# BMI160_SCHEMATIC.net
KiCad netlist of a schematic drawn in EAGLE
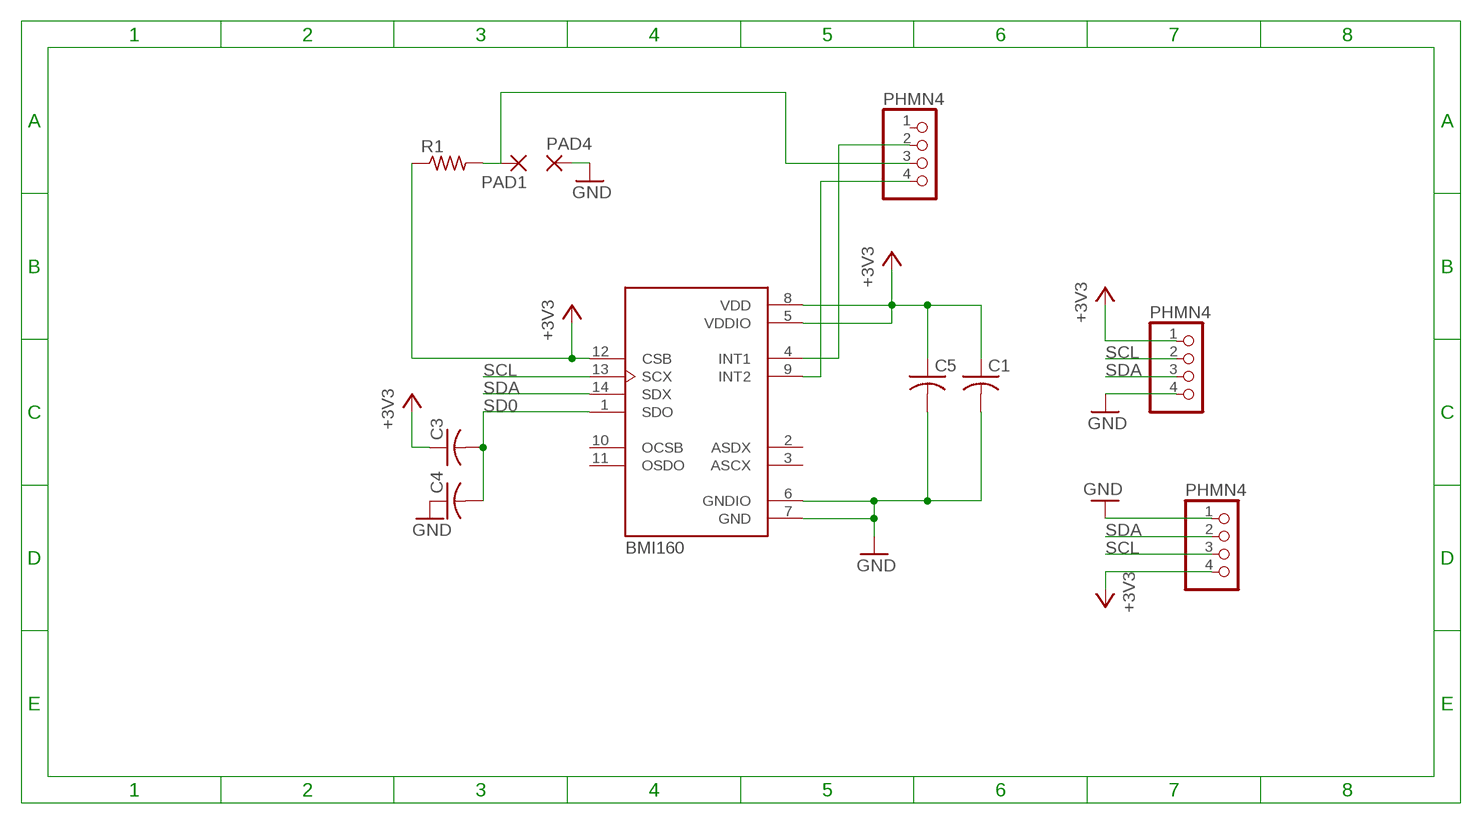
[diagram p0: schematic, sheet 1]

(export (version "E")
  (design (tool "Eeschema 10.0.6"))
  (components
    (comp (ref "C1")
      (value "C-USC0805")
      (footprint "eagle-import:C0805")
      (libsource (lib "eagle-import") (part "C-USC0805"))
    )
    (comp (ref "C3")
      (value "C-USC0805")
      (footprint "eagle-import:C0805")
      (libsource (lib "eagle-import") (part "C-USC0805"))
    )
    (comp (ref "C4")
      (value "C-USC0805")
      (footprint "eagle-import:C0805")
      (libsource (lib "eagle-import") (part "C-USC0805"))
    )
    (comp (ref "C5")
      (value "C-USC0805")
      (footprint "eagle-import:C0805")
      (libsource (lib "eagle-import") (part "C-USC0805"))
    )
    (comp (ref "PAD1")
      (value "WIREPADSMD1,27-254")
      (footprint "eagle-import:SMD1,27-2,54")
      (libsource (lib "eagle-import") (part "WIREPADSMD1,27-254"))
    )
    (comp (ref "PAD4")
      (value "WIREPADSMD1,27-254")
      (footprint "eagle-import:SMD1,27-2,54")
      (libsource (lib "eagle-import") (part "WIREPADSMD1,27-254"))
    )
    (comp (ref "R1")
      (value "CRCW08050000Z0EA")
      (footprint "eagle-import:RES_0805")
      (fields
        (field (name "DIGIKEY_PART_NUMBER") "541-0.0ATR-ND")
        (field (name "MANUFACTURER") "Vishay Dale")
        (field (name "CREATED_BY") "PCBLayout.com")
      )
      (libsource (lib "eagle-import") (part "CRCW08050000Z0EA"))
    )
    (comp (ref "U$1")
      (value "PHMN4")
      (footprint "eagle-import:1X04")
      (libsource (lib "eagle-import") (part "PHMN4"))
    )
    (comp (ref "U$2")
      (value "PHMN4")
      (footprint "eagle-import:1X04")
      (libsource (lib "eagle-import") (part "PHMN4"))
    )
    (comp (ref "U$4")
      (value "PHMN4")
      (footprint "eagle-import:1X04")
      (libsource (lib "eagle-import") (part "PHMN4"))
    )
    (comp (ref "U1")
      (value "BMI160")
      (footprint "eagle-import:PQFN50P300X250X88-14N")
      (fields (field (name "MF") "Bosch"))
      (libsource (lib "eagle-import") (part "BMI160"))
    )
  )
  (nets
    (net (code "1") (name "+3V3") (class "Default")
      (node (ref "C1") (pin "1") (pinfunction "1_1") (pintype "passive"))
      (node (ref "C3") (pin "1") (pinfunction "1_1") (pintype "passive"))
      (node (ref "C5") (pin "1") (pinfunction "1_1") (pintype "passive"))
      (node (ref "R1") (pin "1") (pinfunction "1_1") (pintype "passive"))
      (node (ref "U$1") (pin "1") (pinfunction "1_1") (pintype "passive"))
      (node (ref "U$2") (pin "4") (pinfunction "4_4") (pintype "passive"))
      (node (ref "U1") (pin "12") (pinfunction "CSB_12") (pintype "input"))
      (node (ref "U1") (pin "5") (pinfunction "VDDIO_5") (pintype "power_in"))
      (node (ref "U1") (pin "8") (pinfunction "VDD_8") (pintype "power_in"))
    )
    (net (code "2") (name "/SCL") (class "Default")
      (node (ref "U$1") (pin "2") (pinfunction "2_2") (pintype "passive"))
      (node (ref "U$2") (pin "3") (pinfunction "3_3") (pintype "passive"))
      (node (ref "U1") (pin "13") (pinfunction "SCX_13") (pintype "input"))
    )
    (net (code "3") (name "/SD0") (class "Default")
      (node (ref "C3") (pin "2") (pinfunction "2_2") (pintype "passive"))
      (node (ref "C4") (pin "2") (pinfunction "2_2") (pintype "passive"))
      (node (ref "U1") (pin "1") (pinfunction "SDO_1") (pintype "bidirectional"))
    )
    (net (code "4") (name "/SDA") (class "Default")
      (node (ref "U$1") (pin "3") (pinfunction "3_3") (pintype "passive"))
      (node (ref "U$2") (pin "2") (pinfunction "2_2") (pintype "passive"))
      (node (ref "U1") (pin "14") (pinfunction "SDX_14") (pintype "bidirectional"))
    )
    (net (code "5") (name "GND") (class "Default")
      (node (ref "C1") (pin "2") (pinfunction "2_2") (pintype "passive"))
      (node (ref "C4") (pin "1") (pinfunction "1_1") (pintype "passive"))
      (node (ref "C5") (pin "2") (pinfunction "2_2") (pintype "passive"))
      (node (ref "PAD4") (pin "1") (pinfunction "P_1") (pintype "passive"))
      (node (ref "U$1") (pin "4") (pinfunction "4_4") (pintype "passive"))
      (node (ref "U$2") (pin "1") (pinfunction "1_1") (pintype "passive"))
      (node (ref "U1") (pin "6") (pinfunction "GNDIO_6") (pintype "power_in"))
      (node (ref "U1") (pin "7") (pinfunction "GND_7") (pintype "power_in"))
    )
    (net (code "6") (name "Net-(PAD1-P)") (class "Default")
      (node (ref "PAD1") (pin "1") (pinfunction "P_1") (pintype "passive"))
      (node (ref "R1") (pin "2") (pinfunction "2_2") (pintype "passive"))
      (node (ref "U$4") (pin "3") (pinfunction "3_3") (pintype "passive"))
    )
    (net (code "7") (name "Net-(U1-INT1)") (class "Default")
      (node (ref "U$4") (pin "2") (pinfunction "2_2") (pintype "passive"))
      (node (ref "U1") (pin "4") (pinfunction "INT1_4") (pintype "bidirectional"))
    )
    (net (code "8") (name "Net-(U1-INT2)") (class "Default")
      (node (ref "U$4") (pin "4") (pinfunction "4_4") (pintype "passive"))
      (node (ref "U1") (pin "9") (pinfunction "INT2_9") (pintype "bidirectional"))
    )
    (net (code "9") (name "unconnected-(U$4-Pad1)") (class "Default")
      (node (ref "U$4") (pin "1") (pinfunction "1_1") (pintype "passive"))
    )
    (net (code "10") (name "unconnected-(U1-ASCX-Pad3)") (class "Default")
      (node (ref "U1") (pin "3") (pinfunction "ASCX_3") (pintype "output"))
    )
    (net (code "11") (name "unconnected-(U1-ASDX-Pad2)") (class "Default")
      (node (ref "U1") (pin "2") (pinfunction "ASDX_2") (pintype "bidirectional"))
    )
    (net (code "12") (name "unconnected-(U1-OCSB-Pad10)") (class "Default")
      (node (ref "U1") (pin "10") (pinfunction "OCSB_10") (pintype "bidirectional"))
    )
    (net (code "13") (name "unconnected-(U1-OSDO-Pad11)") (class "Default")
      (node (ref "U1") (pin "11") (pinfunction "OSDO_11") (pintype "bidirectional"))
    )
  )
)
